# igniter.net
KiCad netlist of a schematic drawn in EAGLE
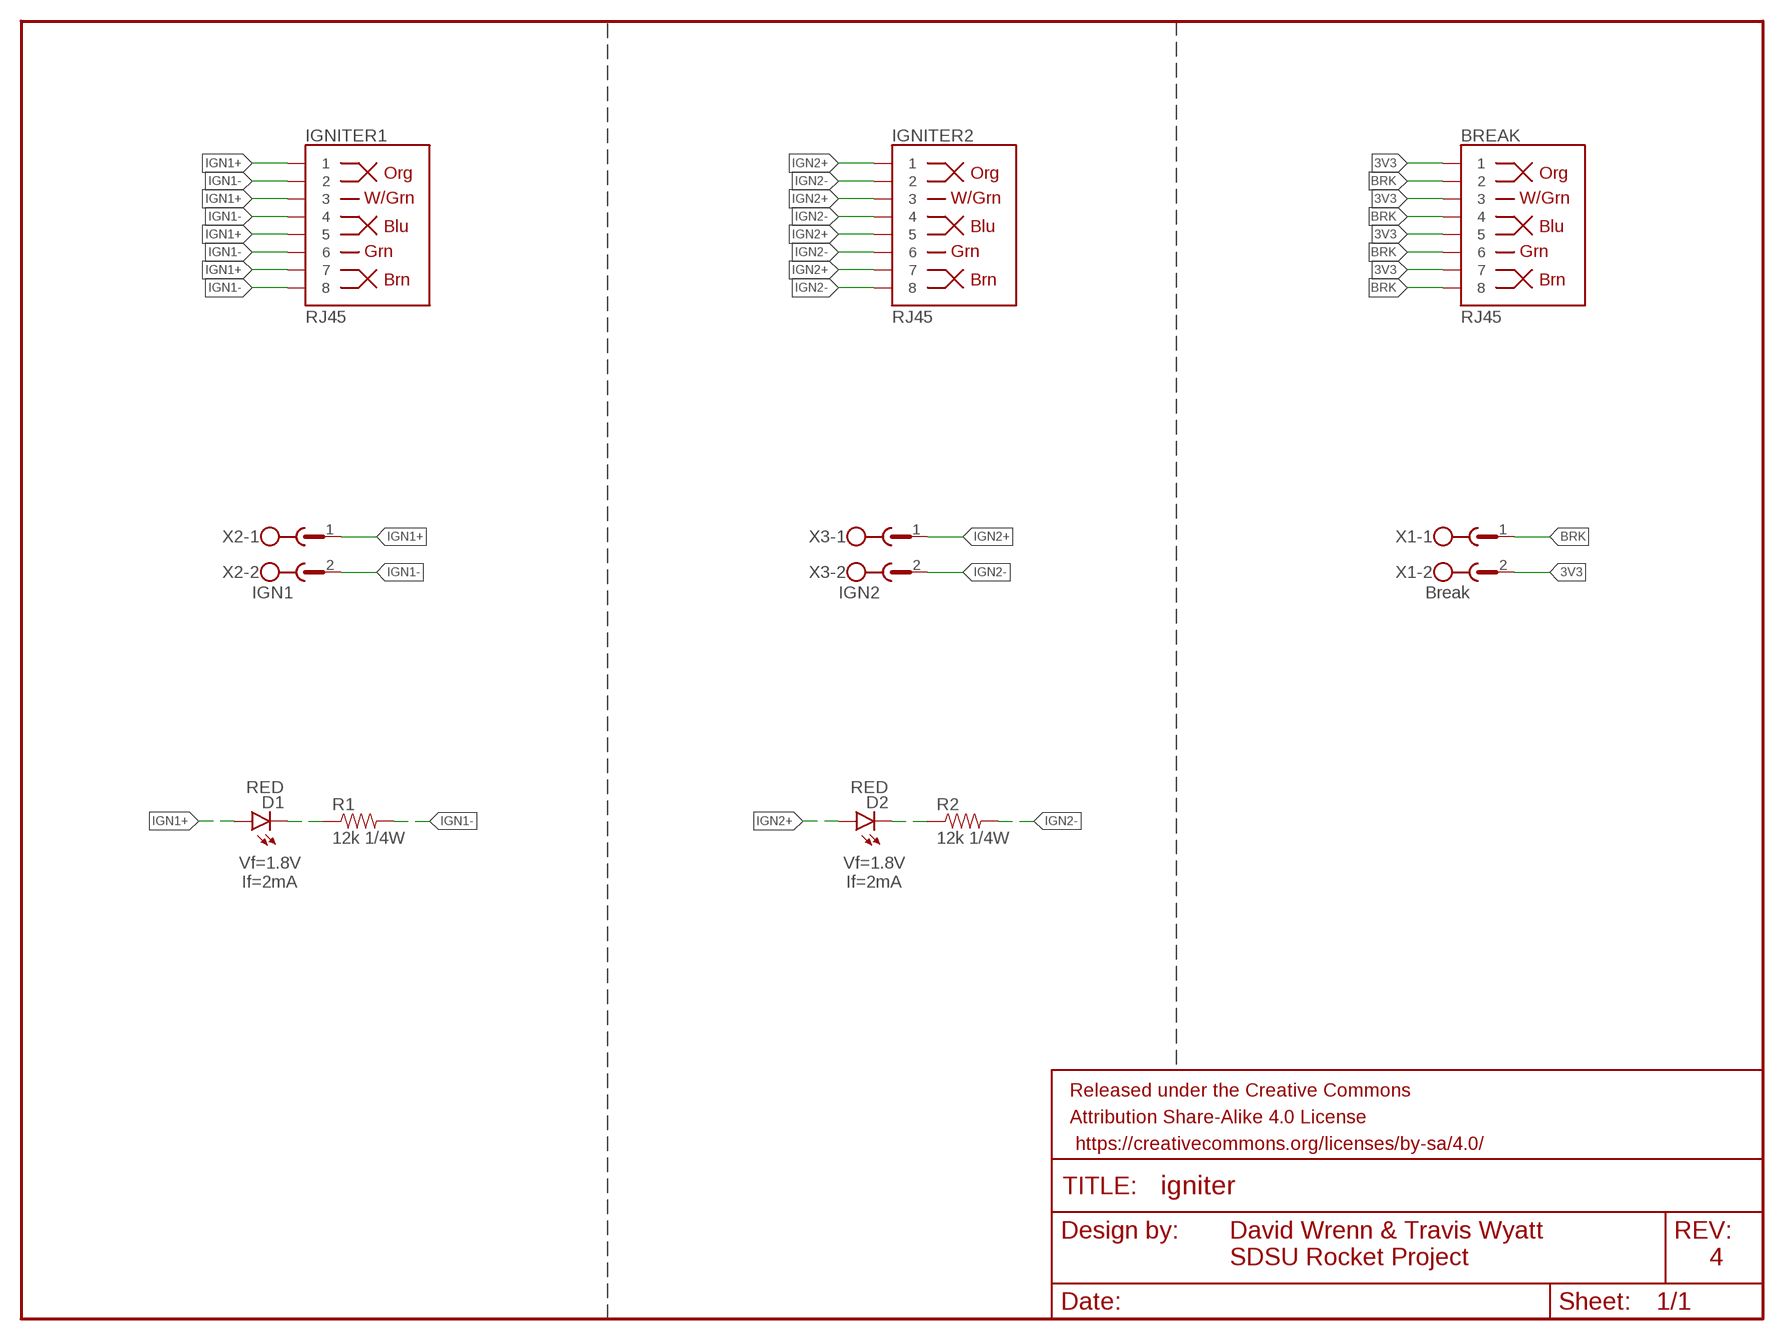
[diagram p0: schematic, sheet 1]

(export (version "E")
  (design (tool "Eeschema 10.0.6"))
  (components
    (comp (ref "BREAK")
      (value "RJ45")
      (footprint "eagle-import:RJ45-8")
      (libsource (lib "eagle-import") (part "RJ45-8PTH"))
    )
    (comp (ref "D1")
      (value "RED")
      (footprint "eagle-import:LED-0603")
      (libsource (lib "eagle-import") (part "LED0603"))
    )
    (comp (ref "D2")
      (value "RED")
      (footprint "eagle-import:LED-0603")
      (libsource (lib "eagle-import") (part "LED0603"))
    )
    (comp (ref "FRAME1")
      (value "FRAME-LETTER")
      (footprint "eagle-import:CREATIVE_COMMONS")
      (fields (field (name "DESIGNER") "NAME"))
      (libsource (lib "eagle-import") (part "FRAME-LETTER"))
    )
    (comp (ref "IGNITER1")
      (value "RJ45")
      (footprint "eagle-import:RJ45-8")
      (libsource (lib "eagle-import") (part "RJ45-8PTH"))
    )
    (comp (ref "IGNITER2")
      (value "RJ45")
      (footprint "eagle-import:RJ45-8")
      (libsource (lib "eagle-import") (part "RJ45-8PTH"))
    )
    (comp (ref "R1")
      (value "12k 1/4W")
      (footprint "eagle-import:0603-RES")
      (libsource (lib "eagle-import") (part "RESISTOR0603-RES"))
    )
    (comp (ref "R2")
      (value "12k 1/4W")
      (footprint "eagle-import:0603-RES")
      (libsource (lib "eagle-import") (part "RESISTOR0603-RES"))
    )
    (comp (ref "X1")
      (value "Break")
      (footprint "eagle-import:MSTBA2")
      (fields (field (name "MF") "FARNELL") (field (name "MPN") "1757242"))
      (libsource (lib "eagle-import") (part "MSTBA2"))
    )
    (comp (ref "X2")
      (value "IGN1")
      (footprint "eagle-import:MSTBA2")
      (fields (field (name "MF") "FARNELL") (field (name "MPN") "1757242"))
      (libsource (lib "eagle-import") (part "MSTBA2"))
    )
    (comp (ref "X3")
      (value "IGN2")
      (footprint "eagle-import:MSTBA2")
      (fields (field (name "MF") "FARNELL") (field (name "MPN") "1757242"))
      (libsource (lib "eagle-import") (part "MSTBA2"))
    )
  )
  (nets
    (net (code "1") (name "3V3") (class "Default")
      (node (ref "BREAK") (pin "1") (pinfunction "1_1") (pintype "bidirectional"))
      (node (ref "BREAK") (pin "3") (pinfunction "3_3") (pintype "bidirectional"))
      (node (ref "BREAK") (pin "5") (pinfunction "5_5") (pintype "bidirectional"))
      (node (ref "BREAK") (pin "7") (pinfunction "7_7") (pintype "bidirectional"))
      (node (ref "X1") (pin "2") (pinfunction "1_2") (pintype "passive"))
    )
    (net (code "2") (name "BRK") (class "Default")
      (node (ref "BREAK") (pin "2") (pinfunction "2_2") (pintype "bidirectional"))
      (node (ref "BREAK") (pin "4") (pinfunction "4_4") (pintype "bidirectional"))
      (node (ref "BREAK") (pin "6") (pinfunction "6_6") (pintype "bidirectional"))
      (node (ref "BREAK") (pin "8") (pinfunction "8_8") (pintype "bidirectional"))
      (node (ref "X1") (pin "1") (pinfunction "1_1") (pintype "passive"))
    )
    (net (code "3") (name "IGN1+") (class "Default")
      (node (ref "D1") (pin "A") (pinfunction "A_A") (pintype "passive"))
      (node (ref "IGNITER1") (pin "1") (pinfunction "1_1") (pintype "bidirectional"))
      (node (ref "IGNITER1") (pin "3") (pinfunction "3_3") (pintype "bidirectional"))
      (node (ref "IGNITER1") (pin "5") (pinfunction "5_5") (pintype "bidirectional"))
      (node (ref "IGNITER1") (pin "7") (pinfunction "7_7") (pintype "bidirectional"))
      (node (ref "X2") (pin "1") (pinfunction "1_1") (pintype "passive"))
    )
    (net (code "4") (name "IGN1-") (class "Default")
      (node (ref "IGNITER1") (pin "2") (pinfunction "2_2") (pintype "bidirectional"))
      (node (ref "IGNITER1") (pin "4") (pinfunction "4_4") (pintype "bidirectional"))
      (node (ref "IGNITER1") (pin "6") (pinfunction "6_6") (pintype "bidirectional"))
      (node (ref "IGNITER1") (pin "8") (pinfunction "8_8") (pintype "bidirectional"))
      (node (ref "R1") (pin "2") (pinfunction "2_2") (pintype "passive"))
      (node (ref "X2") (pin "2") (pinfunction "1_2") (pintype "passive"))
    )
    (net (code "5") (name "IGN2+") (class "Default")
      (node (ref "D2") (pin "A") (pinfunction "A_A") (pintype "passive"))
      (node (ref "IGNITER2") (pin "1") (pinfunction "1_1") (pintype "bidirectional"))
      (node (ref "IGNITER2") (pin "3") (pinfunction "3_3") (pintype "bidirectional"))
      (node (ref "IGNITER2") (pin "5") (pinfunction "5_5") (pintype "bidirectional"))
      (node (ref "IGNITER2") (pin "7") (pinfunction "7_7") (pintype "bidirectional"))
      (node (ref "X3") (pin "1") (pinfunction "1_1") (pintype "passive"))
    )
    (net (code "6") (name "IGN2-") (class "Default")
      (node (ref "IGNITER2") (pin "2") (pinfunction "2_2") (pintype "bidirectional"))
      (node (ref "IGNITER2") (pin "4") (pinfunction "4_4") (pintype "bidirectional"))
      (node (ref "IGNITER2") (pin "6") (pinfunction "6_6") (pintype "bidirectional"))
      (node (ref "IGNITER2") (pin "8") (pinfunction "8_8") (pintype "bidirectional"))
      (node (ref "R2") (pin "2") (pinfunction "2_2") (pintype "passive"))
      (node (ref "X3") (pin "2") (pinfunction "1_2") (pintype "passive"))
    )
    (net (code "7") (name "Net-(D1-PadC)") (class "Default")
      (node (ref "D1") (pin "C") (pinfunction "C_C") (pintype "passive"))
      (node (ref "R1") (pin "1") (pinfunction "1_1") (pintype "passive"))
    )
    (net (code "8") (name "Net-(D2-PadC)") (class "Default")
      (node (ref "D2") (pin "C") (pinfunction "C_C") (pintype "passive"))
      (node (ref "R2") (pin "1") (pinfunction "1_1") (pintype "passive"))
    )
  )
)
